# analog_part.net
KiCad netlist of a schematic drawn in Altium Designer
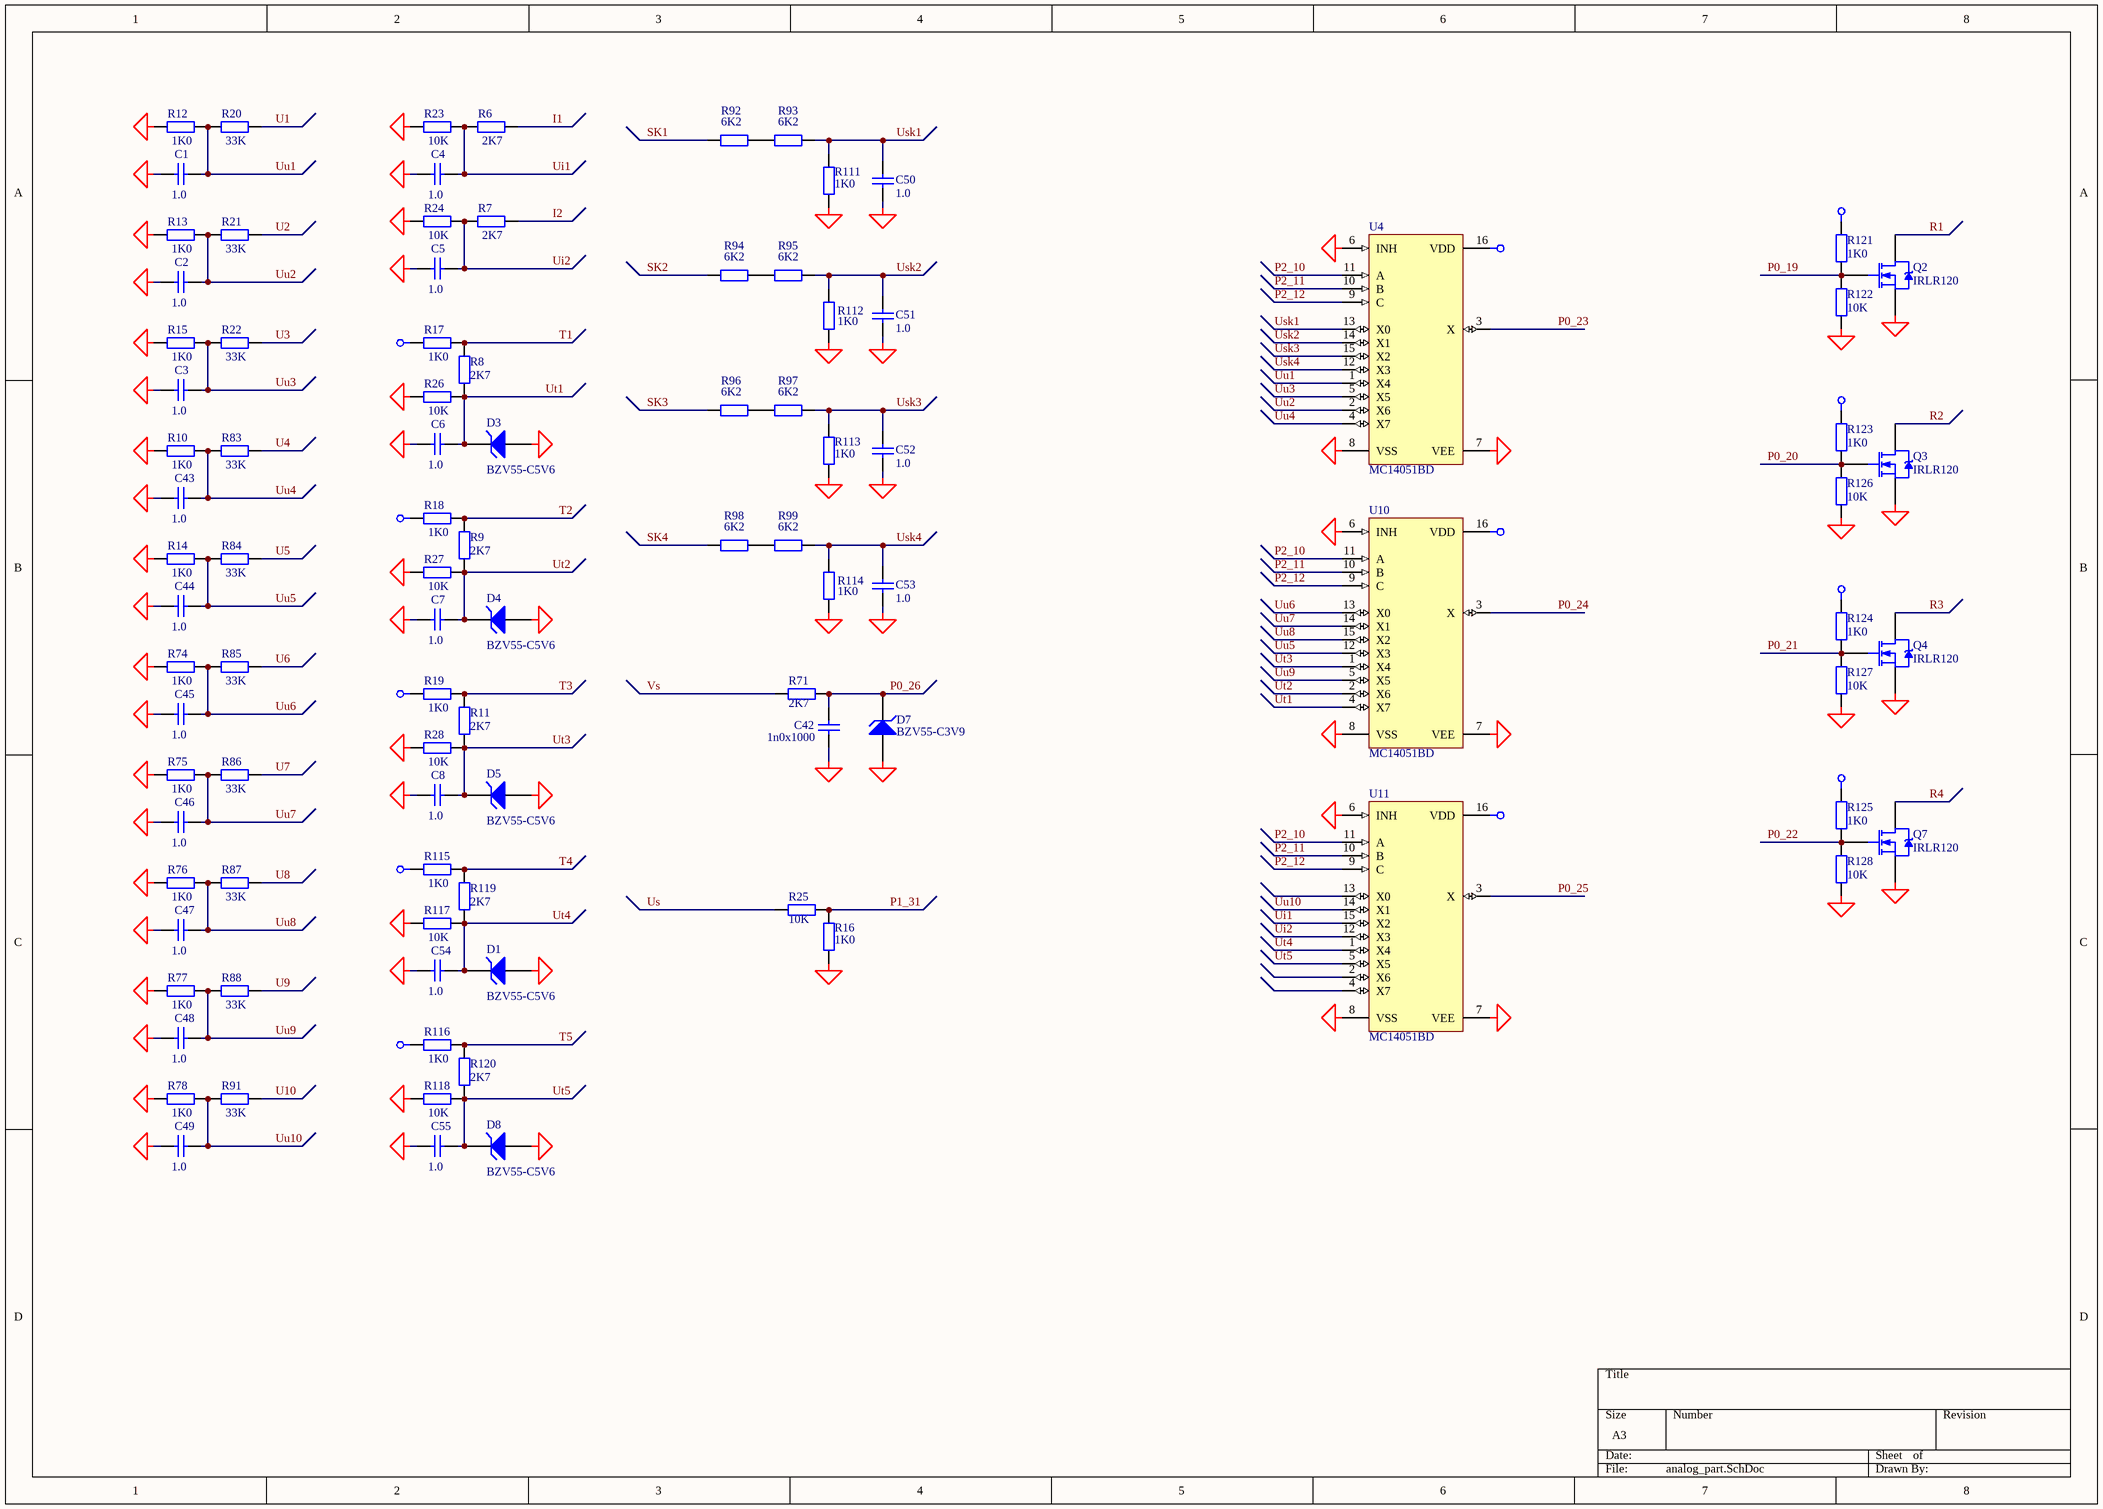
[diagram p0: analog_part.SchDoc]

(export (version "E")
  (design (tool "Eeschema 10.0.6"))
  (components
    (comp (ref "C1")
      (value "1.0")
      (footprint "_1206")
      (description "Capacitor (Semiconductor SIM Model)")
      (fields (field (name "MANUFACTURER") "Generic Components") (field (name "PUBLISHER") "Altium Limited"))
      (libsource (lib "Miscellaneous Devices") (part "Cap Semi"))
    )
    (comp (ref "C2")
      (value "1.0")
      (footprint "_1206")
      (description "Capacitor (Semiconductor SIM Model)")
      (fields (field (name "MANUFACTURER") "Generic Components") (field (name "PUBLISHER") "Altium Limited"))
      (libsource (lib "Miscellaneous Devices") (part "Cap Semi"))
    )
    (comp (ref "C3")
      (value "1.0")
      (footprint "_1206")
      (description "Capacitor (Semiconductor SIM Model)")
      (fields (field (name "MANUFACTURER") "Generic Components") (field (name "PUBLISHER") "Altium Limited"))
      (libsource (lib "Miscellaneous Devices") (part "Cap Semi"))
    )
    (comp (ref "C4")
      (value "1.0")
      (footprint "_1206")
      (description "Capacitor (Semiconductor SIM Model)")
      (fields (field (name "MANUFACTURER") "Generic Components") (field (name "PUBLISHER") "Altium Limited"))
      (libsource (lib "Miscellaneous Devices") (part "Cap Semi"))
    )
    (comp (ref "C5")
      (value "1.0")
      (footprint "_1206")
      (description "Capacitor (Semiconductor SIM Model)")
      (fields (field (name "MANUFACTURER") "Generic Components") (field (name "PUBLISHER") "Altium Limited"))
      (libsource (lib "Miscellaneous Devices") (part "Cap Semi"))
    )
    (comp (ref "C6")
      (value "1.0")
      (footprint "_1206")
      (description "Capacitor (Semiconductor SIM Model)")
      (fields (field (name "MANUFACTURER") "Generic Components") (field (name "PUBLISHER") "Altium Limited"))
      (libsource (lib "Miscellaneous Devices") (part "Cap Semi"))
    )
    (comp (ref "C7")
      (value "1.0")
      (footprint "_1206")
      (description "Capacitor (Semiconductor SIM Model)")
      (fields (field (name "MANUFACTURER") "Generic Components") (field (name "PUBLISHER") "Altium Limited"))
      (libsource (lib "Miscellaneous Devices") (part "Cap Semi"))
    )
    (comp (ref "C8")
      (value "1.0")
      (footprint "_1206")
      (description "Capacitor (Semiconductor SIM Model)")
      (fields (field (name "MANUFACTURER") "Generic Components") (field (name "PUBLISHER") "Altium Limited"))
      (libsource (lib "Miscellaneous Devices") (part "Cap Semi"))
    )
    (comp (ref "C42")
      (value "1n0x1000")
      (footprint "_1206")
      (description "Capacitor (Semiconductor SIM Model)")
      (fields (field (name "MANUFACTURER") "Generic Components") (field (name "PUBLISHER") "Altium Limited"))
      (libsource (lib "") (part "Cap Semi_1"))
    )
    (comp (ref "C43")
      (value "1.0")
      (footprint "_1206")
      (description "Capacitor (Semiconductor SIM Model)")
      (fields (field (name "MANUFACTURER") "Generic Components") (field (name "PUBLISHER") "Altium Limited"))
      (libsource (lib "Miscellaneous Devices") (part "Cap Semi"))
    )
    (comp (ref "C44")
      (value "1.0")
      (footprint "_1206")
      (description "Capacitor (Semiconductor SIM Model)")
      (fields (field (name "MANUFACTURER") "Generic Components") (field (name "PUBLISHER") "Altium Limited"))
      (libsource (lib "Miscellaneous Devices") (part "Cap Semi"))
    )
    (comp (ref "C45")
      (value "1.0")
      (footprint "_1206")
      (description "Capacitor (Semiconductor SIM Model)")
      (fields (field (name "MANUFACTURER") "Generic Components") (field (name "PUBLISHER") "Altium Limited"))
      (libsource (lib "Miscellaneous Devices") (part "Cap Semi"))
    )
    (comp (ref "C46")
      (value "1.0")
      (footprint "_1206")
      (description "Capacitor (Semiconductor SIM Model)")
      (fields (field (name "MANUFACTURER") "Generic Components") (field (name "PUBLISHER") "Altium Limited"))
      (libsource (lib "Miscellaneous Devices") (part "Cap Semi"))
    )
    (comp (ref "C47")
      (value "1.0")
      (footprint "_1206")
      (description "Capacitor (Semiconductor SIM Model)")
      (fields (field (name "MANUFACTURER") "Generic Components") (field (name "PUBLISHER") "Altium Limited"))
      (libsource (lib "Miscellaneous Devices") (part "Cap Semi"))
    )
    (comp (ref "C48")
      (value "1.0")
      (footprint "_1206")
      (description "Capacitor (Semiconductor SIM Model)")
      (fields (field (name "MANUFACTURER") "Generic Components") (field (name "PUBLISHER") "Altium Limited"))
      (libsource (lib "Miscellaneous Devices") (part "Cap Semi"))
    )
    (comp (ref "C49")
      (value "1.0")
      (footprint "_1206")
      (description "Capacitor (Semiconductor SIM Model)")
      (fields (field (name "MANUFACTURER") "Generic Components") (field (name "PUBLISHER") "Altium Limited"))
      (libsource (lib "Miscellaneous Devices") (part "Cap Semi"))
    )
    (comp (ref "C50")
      (value "1.0")
      (footprint "_1206")
      (description "Capacitor (Semiconductor SIM Model)")
      (fields (field (name "MANUFACTURER") "Generic Components") (field (name "PUBLISHER") "Altium Limited"))
      (libsource (lib "Miscellaneous Devices") (part "Cap Semi"))
    )
    (comp (ref "C51")
      (value "1.0")
      (footprint "_1206")
      (description "Capacitor (Semiconductor SIM Model)")
      (fields (field (name "MANUFACTURER") "Generic Components") (field (name "PUBLISHER") "Altium Limited"))
      (libsource (lib "Miscellaneous Devices") (part "Cap Semi"))
    )
    (comp (ref "C52")
      (value "1.0")
      (footprint "_1206")
      (description "Capacitor (Semiconductor SIM Model)")
      (fields (field (name "MANUFACTURER") "Generic Components") (field (name "PUBLISHER") "Altium Limited"))
      (libsource (lib "Miscellaneous Devices") (part "Cap Semi"))
    )
    (comp (ref "C53")
      (value "1.0")
      (footprint "_1206")
      (description "Capacitor (Semiconductor SIM Model)")
      (fields (field (name "MANUFACTURER") "Generic Components") (field (name "PUBLISHER") "Altium Limited"))
      (libsource (lib "Miscellaneous Devices") (part "Cap Semi"))
    )
    (comp (ref "C54")
      (value "1.0")
      (footprint "_1206")
      (description "Capacitor (Semiconductor SIM Model)")
      (fields (field (name "MANUFACTURER") "Generic Components") (field (name "PUBLISHER") "Altium Limited"))
      (libsource (lib "Miscellaneous Devices") (part "Cap Semi"))
    )
    (comp (ref "C55")
      (value "1.0")
      (footprint "_1206")
      (description "Capacitor (Semiconductor SIM Model)")
      (fields (field (name "MANUFACTURER") "Generic Components") (field (name "PUBLISHER") "Altium Limited"))
      (libsource (lib "Miscellaneous Devices") (part "Cap Semi"))
    )
    (comp (ref "D1")
      (value "BZV55-C5V6")
      (footprint "_1206d")
      (description "Zener Diode")
      (fields (field (name "MANUFACTURER") "Generic Components") (field (name "PUBLISHER") "Altium Limited"))
      (libsource (lib "Miscellaneous Devices") (part "D Zener"))
    )
    (comp (ref "D3")
      (value "BZV55-C5V6")
      (footprint "_1206d")
      (description "Zener Diode")
      (fields (field (name "MANUFACTURER") "Generic Components") (field (name "PUBLISHER") "Altium Limited"))
      (libsource (lib "Miscellaneous Devices") (part "D Zener"))
    )
    (comp (ref "D4")
      (value "BZV55-C5V6")
      (footprint "_1206d")
      (description "Zener Diode")
      (fields (field (name "MANUFACTURER") "Generic Components") (field (name "PUBLISHER") "Altium Limited"))
      (libsource (lib "Miscellaneous Devices") (part "D Zener"))
    )
    (comp (ref "D5")
      (value "BZV55-C5V6")
      (footprint "_1206d")
      (description "Zener Diode")
      (fields (field (name "MANUFACTURER") "Generic Components") (field (name "PUBLISHER") "Altium Limited"))
      (libsource (lib "Miscellaneous Devices") (part "D Zener"))
    )
    (comp (ref "D7")
      (value "BZV55-C3V9")
      (footprint "_1206d")
      (description "Zener Diode")
      (fields (field (name "MANUFACTURER") "Generic Components") (field (name "PUBLISHER") "Altium Limited"))
      (libsource (lib "") (part "D Zener_1"))
    )
    (comp (ref "D8")
      (value "BZV55-C5V6")
      (footprint "_1206d")
      (description "Zener Diode")
      (fields (field (name "MANUFACTURER") "Generic Components") (field (name "PUBLISHER") "Altium Limited"))
      (libsource (lib "Miscellaneous Devices") (part "D Zener"))
    )
    (comp (ref "Q2")
      (value "IRLR120")
      (footprint "SIP-G3/E8")
      (description "HEXFET N-Channel Power MOSFET")
      (fields
        (field (name "MANUFACTURER") "International Rectifier")
        (field (name "PUBLISHER") "Altium Limited")
      )
      (libsource (lib "IR Discrete MOSFET") (part "IRFR120"))
    )
    (comp (ref "Q3")
      (value "IRLR120")
      (footprint "SIP-G3/E8")
      (description "HEXFET N-Channel Power MOSFET")
      (fields
        (field (name "MANUFACTURER") "International Rectifier")
        (field (name "PUBLISHER") "Altium Limited")
      )
      (libsource (lib "IR Discrete MOSFET") (part "IRFR120"))
    )
    (comp (ref "Q4")
      (value "IRLR120")
      (footprint "SIP-G3/E8")
      (description "HEXFET N-Channel Power MOSFET")
      (fields
        (field (name "MANUFACTURER") "International Rectifier")
        (field (name "PUBLISHER") "Altium Limited")
      )
      (libsource (lib "IR Discrete MOSFET") (part "IRFR120"))
    )
    (comp (ref "Q7")
      (value "IRLR120")
      (footprint "SIP-G3/E8")
      (description "HEXFET N-Channel Power MOSFET")
      (fields
        (field (name "MANUFACTURER") "International Rectifier")
        (field (name "PUBLISHER") "Altium Limited")
      )
      (libsource (lib "IR Discrete MOSFET") (part "IRFR120"))
    )
    (comp (ref "R6")
      (value "2K7")
      (footprint "_1206")
      (description "Resistor")
      (fields (field (name "MANUFACTURER") "Generic Components") (field (name "PUBLISHER") "Altium Limited"))
      (libsource (lib "Miscellaneous Devices") (part "Res2"))
    )
    (comp (ref "R7")
      (value "2K7")
      (footprint "_1206")
      (description "Resistor")
      (fields (field (name "MANUFACTURER") "Generic Components") (field (name "PUBLISHER") "Altium Limited"))
      (libsource (lib "Miscellaneous Devices") (part "Res2"))
    )
    (comp (ref "R8")
      (value "2K7")
      (footprint "_1206")
      (description "Resistor")
      (fields (field (name "MANUFACTURER") "Generic Components") (field (name "PUBLISHER") "Altium Limited"))
      (libsource (lib "") (part "Res2_3"))
    )
    (comp (ref "R9")
      (value "2K7")
      (footprint "_1206")
      (description "Resistor")
      (fields (field (name "MANUFACTURER") "Generic Components") (field (name "PUBLISHER") "Altium Limited"))
      (libsource (lib "") (part "Res2_3"))
    )
    (comp (ref "R10")
      (value "1K0")
      (footprint "_1206")
      (description "Resistor")
      (fields (field (name "MANUFACTURER") "Generic Components") (field (name "PUBLISHER") "Altium Limited"))
      (libsource (lib "") (part "Res2_1"))
    )
    (comp (ref "R11")
      (value "2K7")
      (footprint "_1206")
      (description "Resistor")
      (fields (field (name "MANUFACTURER") "Generic Components") (field (name "PUBLISHER") "Altium Limited"))
      (libsource (lib "") (part "Res2_3"))
    )
    (comp (ref "R12")
      (value "1K0")
      (footprint "_1206")
      (description "Resistor")
      (fields (field (name "MANUFACTURER") "Generic Components") (field (name "PUBLISHER") "Altium Limited"))
      (libsource (lib "") (part "Res2_1"))
    )
    (comp (ref "R13")
      (value "1K0")
      (footprint "_1206")
      (description "Resistor")
      (fields (field (name "MANUFACTURER") "Generic Components") (field (name "PUBLISHER") "Altium Limited"))
      (libsource (lib "") (part "Res2_1"))
    )
    (comp (ref "R14")
      (value "1K0")
      (footprint "_1206")
      (description "Resistor")
      (fields (field (name "MANUFACTURER") "Generic Components") (field (name "PUBLISHER") "Altium Limited"))
      (libsource (lib "") (part "Res2_1"))
    )
    (comp (ref "R15")
      (value "1K0")
      (footprint "_1206")
      (description "Resistor")
      (fields (field (name "MANUFACTURER") "Generic Components") (field (name "PUBLISHER") "Altium Limited"))
      (libsource (lib "") (part "Res2_1"))
    )
    (comp (ref "R16")
      (value "1K0")
      (footprint "_1206")
      (description "Resistor")
      (fields (field (name "MANUFACTURER") "Generic Components") (field (name "PUBLISHER") "Altium Limited"))
      (libsource (lib "") (part "Res2_2"))
    )
    (comp (ref "R17")
      (value "1K0")
      (footprint "_1206")
      (description "Resistor")
      (fields (field (name "MANUFACTURER") "Generic Components") (field (name "PUBLISHER") "Altium Limited"))
      (libsource (lib "") (part "Res2_1"))
    )
    (comp (ref "R18")
      (value "1K0")
      (footprint "_1206")
      (description "Resistor")
      (fields (field (name "MANUFACTURER") "Generic Components") (field (name "PUBLISHER") "Altium Limited"))
      (libsource (lib "") (part "Res2_1"))
    )
    (comp (ref "R19")
      (value "1K0")
      (footprint "_1206")
      (description "Resistor")
      (fields (field (name "MANUFACTURER") "Generic Components") (field (name "PUBLISHER") "Altium Limited"))
      (libsource (lib "") (part "Res2_1"))
    )
    (comp (ref "R20")
      (value "33K")
      (footprint "_1206")
      (description "Resistor")
      (fields (field (name "MANUFACTURER") "Generic Components") (field (name "PUBLISHER") "Altium Limited"))
      (libsource (lib "Miscellaneous Devices") (part "Res2"))
    )
    (comp (ref "R21")
      (value "33K")
      (footprint "_1206")
      (description "Resistor")
      (fields (field (name "MANUFACTURER") "Generic Components") (field (name "PUBLISHER") "Altium Limited"))
      (libsource (lib "Miscellaneous Devices") (part "Res2"))
    )
    (comp (ref "R22")
      (value "33K")
      (footprint "_1206")
      (description "Resistor")
      (fields (field (name "MANUFACTURER") "Generic Components") (field (name "PUBLISHER") "Altium Limited"))
      (libsource (lib "Miscellaneous Devices") (part "Res2"))
    )
    (comp (ref "R23")
      (value "10K")
      (footprint "_1206")
      (description "Resistor")
      (fields (field (name "MANUFACTURER") "Generic Components") (field (name "PUBLISHER") "Altium Limited"))
      (libsource (lib "Miscellaneous Devices") (part "Res2"))
    )
    (comp (ref "R24")
      (value "10K")
      (footprint "_1206")
      (description "Resistor")
      (fields (field (name "MANUFACTURER") "Generic Components") (field (name "PUBLISHER") "Altium Limited"))
      (libsource (lib "Miscellaneous Devices") (part "Res2"))
    )
    (comp (ref "R25")
      (value "10K")
      (footprint "_1206")
      (description "Resistor")
      (fields (field (name "MANUFACTURER") "Generic Components") (field (name "PUBLISHER") "Altium Limited"))
      (libsource (lib "") (part "Res2_1"))
    )
    (comp (ref "R26")
      (value "10K")
      (footprint "_1206")
      (description "Resistor")
      (fields (field (name "MANUFACTURER") "Generic Components") (field (name "PUBLISHER") "Altium Limited"))
      (libsource (lib "Miscellaneous Devices") (part "Res2"))
    )
    (comp (ref "R27")
      (value "10K")
      (footprint "_1206")
      (description "Resistor")
      (fields (field (name "MANUFACTURER") "Generic Components") (field (name "PUBLISHER") "Altium Limited"))
      (libsource (lib "Miscellaneous Devices") (part "Res2"))
    )
    (comp (ref "R28")
      (value "10K")
      (footprint "_1206")
      (description "Resistor")
      (fields (field (name "MANUFACTURER") "Generic Components") (field (name "PUBLISHER") "Altium Limited"))
      (libsource (lib "Miscellaneous Devices") (part "Res2"))
    )
    (comp (ref "R71")
      (value "2K7")
      (footprint "_1206")
      (description "Resistor")
      (fields (field (name "MANUFACTURER") "Generic Components") (field (name "PUBLISHER") "Altium Limited"))
      (libsource (lib "") (part "Res2_4"))
    )
    (comp (ref "R74")
      (value "1K0")
      (footprint "_1206")
      (description "Resistor")
      (fields (field (name "MANUFACTURER") "Generic Components") (field (name "PUBLISHER") "Altium Limited"))
      (libsource (lib "") (part "Res2_1"))
    )
    (comp (ref "R75")
      (value "1K0")
      (footprint "_1206")
      (description "Resistor")
      (fields (field (name "MANUFACTURER") "Generic Components") (field (name "PUBLISHER") "Altium Limited"))
      (libsource (lib "") (part "Res2_1"))
    )
    (comp (ref "R76")
      (value "1K0")
      (footprint "_1206")
      (description "Resistor")
      (fields (field (name "MANUFACTURER") "Generic Components") (field (name "PUBLISHER") "Altium Limited"))
      (libsource (lib "") (part "Res2_1"))
    )
    (comp (ref "R77")
      (value "1K0")
      (footprint "_1206")
      (description "Resistor")
      (fields (field (name "MANUFACTURER") "Generic Components") (field (name "PUBLISHER") "Altium Limited"))
      (libsource (lib "") (part "Res2_1"))
    )
    (comp (ref "R78")
      (value "1K0")
      (footprint "_1206")
      (description "Resistor")
      (fields (field (name "MANUFACTURER") "Generic Components") (field (name "PUBLISHER") "Altium Limited"))
      (libsource (lib "") (part "Res2_1"))
    )
    (comp (ref "R83")
      (value "33K")
      (footprint "_1206")
      (description "Resistor")
      (fields (field (name "MANUFACTURER") "Generic Components") (field (name "PUBLISHER") "Altium Limited"))
      (libsource (lib "Miscellaneous Devices") (part "Res2"))
    )
    (comp (ref "R84")
      (value "33K")
      (footprint "_1206")
      (description "Resistor")
      (fields (field (name "MANUFACTURER") "Generic Components") (field (name "PUBLISHER") "Altium Limited"))
      (libsource (lib "Miscellaneous Devices") (part "Res2"))
    )
    (comp (ref "R85")
      (value "33K")
      (footprint "_1206")
      (description "Resistor")
      (fields (field (name "MANUFACTURER") "Generic Components") (field (name "PUBLISHER") "Altium Limited"))
      (libsource (lib "Miscellaneous Devices") (part "Res2"))
    )
    (comp (ref "R86")
      (value "33K")
      (footprint "_1206")
      (description "Resistor")
      (fields (field (name "MANUFACTURER") "Generic Components") (field (name "PUBLISHER") "Altium Limited"))
      (libsource (lib "Miscellaneous Devices") (part "Res2"))
    )
    (comp (ref "R87")
      (value "33K")
      (footprint "_1206")
      (description "Resistor")
      (fields (field (name "MANUFACTURER") "Generic Components") (field (name "PUBLISHER") "Altium Limited"))
      (libsource (lib "Miscellaneous Devices") (part "Res2"))
    )
    (comp (ref "R88")
      (value "33K")
      (footprint "_1206")
      (description "Resistor")
      (fields (field (name "MANUFACTURER") "Generic Components") (field (name "PUBLISHER") "Altium Limited"))
      (libsource (lib "Miscellaneous Devices") (part "Res2"))
    )
    (comp (ref "R91")
      (value "33K")
      (footprint "_1206")
      (description "Resistor")
      (fields (field (name "MANUFACTURER") "Generic Components") (field (name "PUBLISHER") "Altium Limited"))
      (libsource (lib "Miscellaneous Devices") (part "Res2"))
    )
    (comp (ref "R92")
      (value "6K2")
      (footprint "_1206")
      (description "Resistor")
      (fields (field (name "MANUFACTURER") "Generic Components") (field (name "PUBLISHER") "Altium Limited"))
      (libsource (lib "Miscellaneous Devices") (part "Res2"))
    )
    (comp (ref "R93")
      (value "6K2")
      (footprint "_1206")
      (description "Resistor")
      (fields (field (name "MANUFACTURER") "Generic Components") (field (name "PUBLISHER") "Altium Limited"))
      (libsource (lib "Miscellaneous Devices") (part "Res2"))
    )
    (comp (ref "R94")
      (value "6K2")
      (footprint "_1206")
      (description "Resistor")
      (fields (field (name "MANUFACTURER") "Generic Components") (field (name "PUBLISHER") "Altium Limited"))
      (libsource (lib "Miscellaneous Devices") (part "Res2"))
    )
    (comp (ref "R95")
      (value "6K2")
      (footprint "_1206")
      (description "Resistor")
      (fields (field (name "MANUFACTURER") "Generic Components") (field (name "PUBLISHER") "Altium Limited"))
      (libsource (lib "Miscellaneous Devices") (part "Res2"))
    )
    (comp (ref "R96")
      (value "6K2")
      (footprint "_1206")
      (description "Resistor")
      (fields (field (name "MANUFACTURER") "Generic Components") (field (name "PUBLISHER") "Altium Limited"))
      (libsource (lib "Miscellaneous Devices") (part "Res2"))
    )
    (comp (ref "R97")
      (value "6K2")
      (footprint "_1206")
      (description "Resistor")
      (fields (field (name "MANUFACTURER") "Generic Components") (field (name "PUBLISHER") "Altium Limited"))
      (libsource (lib "Miscellaneous Devices") (part "Res2"))
    )
    (comp (ref "R98")
      (value "6K2")
      (footprint "_1206")
      (description "Resistor")
      (fields (field (name "MANUFACTURER") "Generic Components") (field (name "PUBLISHER") "Altium Limited"))
      (libsource (lib "Miscellaneous Devices") (part "Res2"))
    )
    (comp (ref "R99")
      (value "6K2")
      (footprint "_1206")
      (description "Resistor")
      (fields (field (name "MANUFACTURER") "Generic Components") (field (name "PUBLISHER") "Altium Limited"))
      (libsource (lib "Miscellaneous Devices") (part "Res2"))
    )
    (comp (ref "R111")
      (value "1K0")
      (footprint "_1206")
      (description "Resistor")
      (fields (field (name "MANUFACTURER") "Generic Components") (field (name "PUBLISHER") "Altium Limited"))
      (libsource (lib "") (part "Res2_3"))
    )
    (comp (ref "R112")
      (value "1K0")
      (footprint "_1206")
      (description "Resistor")
      (fields (field (name "MANUFACTURER") "Generic Components") (field (name "PUBLISHER") "Altium Limited"))
      (libsource (lib "") (part "Res2_3"))
    )
    (comp (ref "R113")
      (value "1K0")
      (footprint "_1206")
      (description "Resistor")
      (fields (field (name "MANUFACTURER") "Generic Components") (field (name "PUBLISHER") "Altium Limited"))
      (libsource (lib "") (part "Res2_3"))
    )
    (comp (ref "R114")
      (value "1K0")
      (footprint "_1206")
      (description "Resistor")
      (fields (field (name "MANUFACTURER") "Generic Components") (field (name "PUBLISHER") "Altium Limited"))
      (libsource (lib "") (part "Res2_3"))
    )
    (comp (ref "R115")
      (value "1K0")
      (footprint "_1206")
      (description "Resistor")
      (fields (field (name "MANUFACTURER") "Generic Components") (field (name "PUBLISHER") "Altium Limited"))
      (libsource (lib "") (part "Res2_1"))
    )
    (comp (ref "R116")
      (value "1K0")
      (footprint "_1206")
      (description "Resistor")
      (fields (field (name "MANUFACTURER") "Generic Components") (field (name "PUBLISHER") "Altium Limited"))
      (libsource (lib "") (part "Res2_1"))
    )
    (comp (ref "R117")
      (value "10K")
      (footprint "_1206")
      (description "Resistor")
      (fields (field (name "MANUFACTURER") "Generic Components") (field (name "PUBLISHER") "Altium Limited"))
      (libsource (lib "Miscellaneous Devices") (part "Res2"))
    )
    (comp (ref "R118")
      (value "10K")
      (footprint "_1206")
      (description "Resistor")
      (fields (field (name "MANUFACTURER") "Generic Components") (field (name "PUBLISHER") "Altium Limited"))
      (libsource (lib "Miscellaneous Devices") (part "Res2"))
    )
    (comp (ref "R119")
      (value "2K7")
      (footprint "_1206")
      (description "Resistor")
      (fields (field (name "MANUFACTURER") "Generic Components") (field (name "PUBLISHER") "Altium Limited"))
      (libsource (lib "") (part "Res2_3"))
    )
    (comp (ref "R120")
      (value "2K7")
      (footprint "_1206")
      (description "Resistor")
      (fields (field (name "MANUFACTURER") "Generic Components") (field (name "PUBLISHER") "Altium Limited"))
      (libsource (lib "") (part "Res2_3"))
    )
    (comp (ref "R121")
      (value "1K0")
      (footprint "_1206")
      (description "Resistor")
      (fields (field (name "MANUFACTURER") "Generic Components") (field (name "PUBLISHER") "Altium Limited"))
      (libsource (lib "") (part "Res2_3"))
    )
    (comp (ref "R122")
      (value "10K")
      (footprint "_1206")
      (description "Resistor")
      (fields (field (name "MANUFACTURER") "Generic Components") (field (name "PUBLISHER") "Altium Limited"))
      (libsource (lib "") (part "Res2_2"))
    )
    (comp (ref "R123")
      (value "1K0")
      (footprint "_1206")
      (description "Resistor")
      (fields (field (name "MANUFACTURER") "Generic Components") (field (name "PUBLISHER") "Altium Limited"))
      (libsource (lib "") (part "Res2_3"))
    )
    (comp (ref "R124")
      (value "1K0")
      (footprint "_1206")
      (description "Resistor")
      (fields (field (name "MANUFACTURER") "Generic Components") (field (name "PUBLISHER") "Altium Limited"))
      (libsource (lib "") (part "Res2_3"))
    )
    (comp (ref "R125")
      (value "1K0")
      (footprint "_1206")
      (description "Resistor")
      (fields (field (name "MANUFACTURER") "Generic Components") (field (name "PUBLISHER") "Altium Limited"))
      (libsource (lib "") (part "Res2_3"))
    )
    (comp (ref "R126")
      (value "10K")
      (footprint "_1206")
      (description "Resistor")
      (fields (field (name "MANUFACTURER") "Generic Components") (field (name "PUBLISHER") "Altium Limited"))
      (libsource (lib "") (part "Res2_2"))
    )
    (comp (ref "R127")
      (value "10K")
      (footprint "_1206")
      (description "Resistor")
      (fields (field (name "MANUFACTURER") "Generic Components") (field (name "PUBLISHER") "Altium Limited"))
      (libsource (lib "") (part "Res2_2"))
    )
    (comp (ref "R128")
      (value "10K")
      (footprint "_1206")
      (description "Resistor")
      (fields (field (name "MANUFACTURER") "Generic Components") (field (name "PUBLISHER") "Altium Limited"))
      (libsource (lib "") (part "Res2_2"))
    )
    (comp (ref "U4")
      (value "MC14051BD")
      (footprint "SO-G16/C5.85")
      (description "8-Channel Analog Multiplexer/Demultiplexer")
      (fields (field (name "MANUFACTURER") "ON Semiconductor") (field (name "PUBLISHER") "Altium Limited"))
      (libsource (lib "ON Semi Logic Multiplexer") (part "MC14051BD"))
    )
    (comp (ref "U10")
      (value "MC14051BD")
      (footprint "SO-G16/C5.85")
      (description "8-Channel Analog Multiplexer/Demultiplexer")
      (fields (field (name "MANUFACTURER") "ON Semiconductor") (field (name "PUBLISHER") "Altium Limited"))
      (libsource (lib "ON Semi Logic Multiplexer") (part "MC14051BD"))
    )
    (comp (ref "U11")
      (value "MC14051BD")
      (footprint "SO-G16/C5.85")
      (description "8-Channel Analog Multiplexer/Demultiplexer")
      (fields (field (name "MANUFACTURER") "ON Semiconductor") (field (name "PUBLISHER") "Altium Limited"))
      (libsource (lib "ON Semi Logic Multiplexer") (part "MC14051BD"))
    )
  )
  (nets
    (net (code "1") (name "+3v3") (class "Default")
      (node (ref "U10") (pin "16") (pinfunction "VDD_16") (pintype "power_in"))
      (node (ref "U11") (pin "16") (pinfunction "VDD_16") (pintype "power_in"))
      (node (ref "U4") (pin "16") (pinfunction "VDD_16") (pintype "power_in"))
    )
    (net (code "2") (name "+5v") (class "Default")
      (node (ref "R115") (pin "2") (pinfunction "2_2") (pintype "passive"))
      (node (ref "R116") (pin "2") (pinfunction "2_2") (pintype "passive"))
      (node (ref "R121") (pin "2") (pinfunction "2_2") (pintype "passive"))
      (node (ref "R123") (pin "2") (pinfunction "2_2") (pintype "passive"))
      (node (ref "R124") (pin "2") (pinfunction "2_2") (pintype "passive"))
      (node (ref "R125") (pin "2") (pinfunction "2_2") (pintype "passive"))
      (node (ref "R17") (pin "2") (pinfunction "2_2") (pintype "passive"))
      (node (ref "R18") (pin "2") (pinfunction "2_2") (pintype "passive"))
      (node (ref "R19") (pin "2") (pinfunction "2_2") (pintype "passive"))
    )
    (net (code "3") (name "/I1") (class "Default")
      (node (ref "R6") (pin "2") (pinfunction "2_2") (pintype "passive"))
    )
    (net (code "4") (name "/I2") (class "Default")
      (node (ref "R7") (pin "2") (pinfunction "2_2") (pintype "passive"))
    )
    (net (code "5") (name "/P0_19") (class "Default")
      (node (ref "Q2") (pin "1") (pinfunction "G_1") (pintype "passive"))
      (node (ref "R121") (pin "1") (pinfunction "1_1") (pintype "passive"))
      (node (ref "R122") (pin "1") (pinfunction "1_1") (pintype "passive"))
    )
    (net (code "6") (name "/P0_20") (class "Default")
      (node (ref "Q3") (pin "1") (pinfunction "G_1") (pintype "passive"))
      (node (ref "R123") (pin "1") (pinfunction "1_1") (pintype "passive"))
      (node (ref "R126") (pin "1") (pinfunction "1_1") (pintype "passive"))
    )
    (net (code "7") (name "/P0_21") (class "Default")
      (node (ref "Q4") (pin "1") (pinfunction "G_1") (pintype "passive"))
      (node (ref "R124") (pin "1") (pinfunction "1_1") (pintype "passive"))
      (node (ref "R127") (pin "1") (pinfunction "1_1") (pintype "passive"))
    )
    (net (code "8") (name "/P0_22") (class "Default")
      (node (ref "Q7") (pin "1") (pinfunction "G_1") (pintype "passive"))
      (node (ref "R125") (pin "1") (pinfunction "1_1") (pintype "passive"))
      (node (ref "R128") (pin "1") (pinfunction "1_1") (pintype "passive"))
    )
    (net (code "9") (name "/P0_23") (class "Default")
      (node (ref "U4") (pin "3") (pinfunction "X_3") (pintype "bidirectional"))
    )
    (net (code "10") (name "/P0_24") (class "Default")
      (node (ref "U10") (pin "3") (pinfunction "X_3") (pintype "bidirectional"))
    )
    (net (code "11") (name "/P0_25") (class "Default")
      (node (ref "U11") (pin "3") (pinfunction "X_3") (pintype "bidirectional"))
    )
    (net (code "12") (name "/P0_26") (class "Default")
      (node (ref "C42") (pin "1") (pinfunction "1_1") (pintype "passive"))
      (node (ref "D7") (pin "2") (pinfunction "K_2") (pintype "passive"))
      (node (ref "R71") (pin "1") (pinfunction "1_1") (pintype "passive"))
    )
    (net (code "13") (name "/P1_31") (class "Default")
      (node (ref "R16") (pin "1") (pinfunction "1_1") (pintype "passive"))
      (node (ref "R25") (pin "1") (pinfunction "1_1") (pintype "passive"))
    )
    (net (code "14") (name "/P2_10") (class "Default")
      (node (ref "U10") (pin "11") (pinfunction "A_11") (pintype "input"))
      (node (ref "U11") (pin "11") (pinfunction "A_11") (pintype "input"))
      (node (ref "U4") (pin "11") (pinfunction "A_11") (pintype "input"))
    )
    (net (code "15") (name "/P2_11") (class "Default")
      (node (ref "U10") (pin "10") (pinfunction "B_10") (pintype "input"))
      (node (ref "U11") (pin "10") (pinfunction "B_10") (pintype "input"))
      (node (ref "U4") (pin "10") (pinfunction "B_10") (pintype "input"))
    )
    (net (code "16") (name "/P2_12") (class "Default")
      (node (ref "U10") (pin "9") (pinfunction "C_9") (pintype "input"))
      (node (ref "U11") (pin "9") (pinfunction "C_9") (pintype "input"))
      (node (ref "U4") (pin "9") (pinfunction "C_9") (pintype "input"))
    )
    (net (code "17") (name "/R1") (class "Default")
      (node (ref "Q2") (pin "4") (pinfunction "D_4") (pintype "passive"))
    )
    (net (code "18") (name "/R2") (class "Default")
      (node (ref "Q3") (pin "4") (pinfunction "D_4") (pintype "passive"))
    )
    (net (code "19") (name "/R3") (class "Default")
      (node (ref "Q4") (pin "4") (pinfunction "D_4") (pintype "passive"))
    )
    (net (code "20") (name "/R4") (class "Default")
      (node (ref "Q7") (pin "4") (pinfunction "D_4") (pintype "passive"))
    )
    (net (code "21") (name "/SK1") (class "Default")
      (node (ref "R92") (pin "1") (pinfunction "1_1") (pintype "passive"))
    )
    (net (code "22") (name "/SK2") (class "Default")
      (node (ref "R94") (pin "1") (pinfunction "1_1") (pintype "passive"))
    )
    (net (code "23") (name "/SK3") (class "Default")
      (node (ref "R96") (pin "1") (pinfunction "1_1") (pintype "passive"))
    )
    (net (code "24") (name "/SK4") (class "Default")
      (node (ref "R98") (pin "1") (pinfunction "1_1") (pintype "passive"))
    )
    (net (code "25") (name "/T1") (class "Default")
      (node (ref "R17") (pin "1") (pinfunction "1_1") (pintype "passive"))
      (node (ref "R8") (pin "2") (pinfunction "2_2") (pintype "passive"))
    )
    (net (code "26") (name "/T2") (class "Default")
      (node (ref "R18") (pin "1") (pinfunction "1_1") (pintype "passive"))
      (node (ref "R9") (pin "2") (pinfunction "2_2") (pintype "passive"))
    )
    (net (code "27") (name "/T3") (class "Default")
      (node (ref "R11") (pin "2") (pinfunction "2_2") (pintype "passive"))
      (node (ref "R19") (pin "1") (pinfunction "1_1") (pintype "passive"))
    )
    (net (code "28") (name "/T4") (class "Default")
      (node (ref "R115") (pin "1") (pinfunction "1_1") (pintype "passive"))
      (node (ref "R119") (pin "2") (pinfunction "2_2") (pintype "passive"))
    )
    (net (code "29") (name "/T5") (class "Default")
      (node (ref "R116") (pin "1") (pinfunction "1_1") (pintype "passive"))
      (node (ref "R120") (pin "2") (pinfunction "2_2") (pintype "passive"))
    )
    (net (code "30") (name "/U1") (class "Default")
      (node (ref "R20") (pin "2") (pinfunction "2_2") (pintype "passive"))
    )
    (net (code "31") (name "/U2") (class "Default")
      (node (ref "R21") (pin "2") (pinfunction "2_2") (pintype "passive"))
    )
    (net (code "32") (name "/U3") (class "Default")
      (node (ref "R22") (pin "2") (pinfunction "2_2") (pintype "passive"))
    )
    (net (code "33") (name "/U4") (class "Default")
      (node (ref "R83") (pin "2") (pinfunction "2_2") (pintype "passive"))
    )
    (net (code "34") (name "/U5") (class "Default")
      (node (ref "R84") (pin "2") (pinfunction "2_2") (pintype "passive"))
    )
    (net (code "35") (name "/U6") (class "Default")
      (node (ref "R85") (pin "2") (pinfunction "2_2") (pintype "passive"))
    )
    (net (code "36") (name "/U7") (class "Default")
      (node (ref "R86") (pin "2") (pinfunction "2_2") (pintype "passive"))
    )
    (net (code "37") (name "/U8") (class "Default")
      (node (ref "R87") (pin "2") (pinfunction "2_2") (pintype "passive"))
    )
    (net (code "38") (name "/U9") (class "Default")
      (node (ref "R88") (pin "2") (pinfunction "2_2") (pintype "passive"))
    )
    (net (code "39") (name "/U10") (class "Default")
      (node (ref "R91") (pin "2") (pinfunction "2_2") (pintype "passive"))
    )
    (net (code "40") (name "/Ui1") (class "Default")
      (node (ref "C4") (pin "1") (pinfunction "1_1") (pintype "passive"))
      (node (ref "R23") (pin "2") (pinfunction "2_2") (pintype "passive"))
      (node (ref "R6") (pin "1") (pinfunction "1_1") (pintype "passive"))
      (node (ref "U11") (pin "15") (pinfunction "X2_15") (pintype "bidirectional"))
    )
    (net (code "41") (name "/Ui2") (class "Default")
      (node (ref "C5") (pin "1") (pinfunction "1_1") (pintype "passive"))
      (node (ref "R24") (pin "2") (pinfunction "2_2") (pintype "passive"))
      (node (ref "R7") (pin "1") (pinfunction "1_1") (pintype "passive"))
      (node (ref "U11") (pin "12") (pinfunction "X3_12") (pintype "bidirectional"))
    )
    (net (code "42") (name "/Us") (class "Default")
      (node (ref "R25") (pin "2") (pinfunction "2_2") (pintype "passive"))
    )
    (net (code "43") (name "/Usk1") (class "Default")
      (node (ref "C50") (pin "1") (pinfunction "1_1") (pintype "passive"))
      (node (ref "R111") (pin "2") (pinfunction "2_2") (pintype "passive"))
      (node (ref "R93") (pin "2") (pinfunction "2_2") (pintype "passive"))
      (node (ref "U4") (pin "13") (pinfunction "X0_13") (pintype "bidirectional"))
    )
    (net (code "44") (name "/Usk2") (class "Default")
      (node (ref "C51") (pin "1") (pinfunction "1_1") (pintype "passive"))
      (node (ref "R112") (pin "2") (pinfunction "2_2") (pintype "passive"))
      (node (ref "R95") (pin "2") (pinfunction "2_2") (pintype "passive"))
      (node (ref "U4") (pin "14") (pinfunction "X1_14") (pintype "bidirectional"))
    )
    (net (code "45") (name "/Usk3") (class "Default")
      (node (ref "C52") (pin "1") (pinfunction "1_1") (pintype "passive"))
      (node (ref "R113") (pin "2") (pinfunction "2_2") (pintype "passive"))
      (node (ref "R97") (pin "2") (pinfunction "2_2") (pintype "passive"))
      (node (ref "U4") (pin "15") (pinfunction "X2_15") (pintype "bidirectional"))
    )
    (net (code "46") (name "/Usk4") (class "Default")
      (node (ref "C53") (pin "1") (pinfunction "1_1") (pintype "passive"))
      (node (ref "R114") (pin "2") (pinfunction "2_2") (pintype "passive"))
      (node (ref "R99") (pin "2") (pinfunction "2_2") (pintype "passive"))
      (node (ref "U4") (pin "12") (pinfunction "X3_12") (pintype "bidirectional"))
    )
    (net (code "47") (name "/Ut1") (class "Default")
      (node (ref "C6") (pin "1") (pinfunction "1_1") (pintype "passive"))
      (node (ref "D3") (pin "2") (pinfunction "K_2") (pintype "passive"))
      (node (ref "R26") (pin "2") (pinfunction "2_2") (pintype "passive"))
      (node (ref "R8") (pin "1") (pinfunction "1_1") (pintype "passive"))
      (node (ref "U10") (pin "4") (pinfunction "X7_4") (pintype "bidirectional"))
    )
    (net (code "48") (name "/Ut2") (class "Default")
      (node (ref "C7") (pin "1") (pinfunction "1_1") (pintype "passive"))
      (node (ref "D4") (pin "2") (pinfunction "K_2") (pintype "passive"))
      (node (ref "R27") (pin "2") (pinfunction "2_2") (pintype "passive"))
      (node (ref "R9") (pin "1") (pinfunction "1_1") (pintype "passive"))
      (node (ref "U10") (pin "2") (pinfunction "X6_2") (pintype "bidirectional"))
    )
    (net (code "49") (name "/Ut3") (class "Default")
      (node (ref "C8") (pin "1") (pinfunction "1_1") (pintype "passive"))
      (node (ref "D5") (pin "2") (pinfunction "K_2") (pintype "passive"))
      (node (ref "R11") (pin "1") (pinfunction "1_1") (pintype "passive"))
      (node (ref "R28") (pin "2") (pinfunction "2_2") (pintype "passive"))
      (node (ref "U10") (pin "1") (pinfunction "X4_1") (pintype "bidirectional"))
    )
    (net (code "50") (name "/Ut4") (class "Default")
      (node (ref "C54") (pin "1") (pinfunction "1_1") (pintype "passive"))
      (node (ref "D1") (pin "2") (pinfunction "K_2") (pintype "passive"))
      (node (ref "R117") (pin "2") (pinfunction "2_2") (pintype "passive"))
      (node (ref "R119") (pin "1") (pinfunction "1_1") (pintype "passive"))
      (node (ref "U11") (pin "1") (pinfunction "X4_1") (pintype "bidirectional"))
    )
    (net (code "51") (name "/Ut5") (class "Default")
      (node (ref "C55") (pin "1") (pinfunction "1_1") (pintype "passive"))
      (node (ref "D8") (pin "2") (pinfunction "K_2") (pintype "passive"))
      (node (ref "R118") (pin "2") (pinfunction "2_2") (pintype "passive"))
      (node (ref "R120") (pin "1") (pinfunction "1_1") (pintype "passive"))
      (node (ref "U11") (pin "5") (pinfunction "X5_5") (pintype "bidirectional"))
    )
    (net (code "52") (name "/Uu1") (class "Default")
      (node (ref "C1") (pin "1") (pinfunction "1_1") (pintype "passive"))
      (node (ref "R12") (pin "1") (pinfunction "1_1") (pintype "passive"))
      (node (ref "R20") (pin "1") (pinfunction "1_1") (pintype "passive"))
      (node (ref "U4") (pin "1") (pinfunction "X4_1") (pintype "bidirectional"))
    )
    (net (code "53") (name "/Uu2") (class "Default")
      (node (ref "C2") (pin "1") (pinfunction "1_1") (pintype "passive"))
      (node (ref "R13") (pin "1") (pinfunction "1_1") (pintype "passive"))
      (node (ref "R21") (pin "1") (pinfunction "1_1") (pintype "passive"))
      (node (ref "U4") (pin "2") (pinfunction "X6_2") (pintype "bidirectional"))
    )
    (net (code "54") (name "/Uu3") (class "Default")
      (node (ref "C3") (pin "1") (pinfunction "1_1") (pintype "passive"))
      (node (ref "R15") (pin "1") (pinfunction "1_1") (pintype "passive"))
      (node (ref "R22") (pin "1") (pinfunction "1_1") (pintype "passive"))
      (node (ref "U4") (pin "5") (pinfunction "X5_5") (pintype "bidirectional"))
    )
    (net (code "55") (name "/Uu4") (class "Default")
      (node (ref "C43") (pin "1") (pinfunction "1_1") (pintype "passive"))
      (node (ref "R10") (pin "1") (pinfunction "1_1") (pintype "passive"))
      (node (ref "R83") (pin "1") (pinfunction "1_1") (pintype "passive"))
      (node (ref "U4") (pin "4") (pinfunction "X7_4") (pintype "bidirectional"))
    )
    (net (code "56") (name "/Uu5") (class "Default")
      (node (ref "C44") (pin "1") (pinfunction "1_1") (pintype "passive"))
      (node (ref "R14") (pin "1") (pinfunction "1_1") (pintype "passive"))
      (node (ref "R84") (pin "1") (pinfunction "1_1") (pintype "passive"))
      (node (ref "U10") (pin "12") (pinfunction "X3_12") (pintype "bidirectional"))
    )
    (net (code "57") (name "/Uu6") (class "Default")
      (node (ref "C45") (pin "1") (pinfunction "1_1") (pintype "passive"))
      (node (ref "R74") (pin "1") (pinfunction "1_1") (pintype "passive"))
      (node (ref "R85") (pin "1") (pinfunction "1_1") (pintype "passive"))
      (node (ref "U10") (pin "13") (pinfunction "X0_13") (pintype "bidirectional"))
    )
    (net (code "58") (name "/Uu7") (class "Default")
      (node (ref "C46") (pin "1") (pinfunction "1_1") (pintype "passive"))
      (node (ref "R75") (pin "1") (pinfunction "1_1") (pintype "passive"))
      (node (ref "R86") (pin "1") (pinfunction "1_1") (pintype "passive"))
      (node (ref "U10") (pin "14") (pinfunction "X1_14") (pintype "bidirectional"))
    )
    (net (code "59") (name "/Uu8") (class "Default")
      (node (ref "C47") (pin "1") (pinfunction "1_1") (pintype "passive"))
      (node (ref "R76") (pin "1") (pinfunction "1_1") (pintype "passive"))
      (node (ref "R87") (pin "1") (pinfunction "1_1") (pintype "passive"))
      (node (ref "U10") (pin "15") (pinfunction "X2_15") (pintype "bidirectional"))
    )
    (net (code "60") (name "/Uu9") (class "Default")
      (node (ref "C48") (pin "1") (pinfunction "1_1") (pintype "passive"))
      (node (ref "R77") (pin "1") (pinfunction "1_1") (pintype "passive"))
      (node (ref "R88") (pin "1") (pinfunction "1_1") (pintype "passive"))
      (node (ref "U10") (pin "5") (pinfunction "X5_5") (pintype "bidirectional"))
    )
    (net (code "61") (name "/Uu10") (class "Default")
      (node (ref "C49") (pin "1") (pinfunction "1_1") (pintype "passive"))
      (node (ref "R78") (pin "1") (pinfunction "1_1") (pintype "passive"))
      (node (ref "R91") (pin "1") (pinfunction "1_1") (pintype "passive"))
      (node (ref "U11") (pin "14") (pinfunction "X1_14") (pintype "bidirectional"))
    )
    (net (code "62") (name "/Vs") (class "Default")
      (node (ref "R71") (pin "2") (pinfunction "2_2") (pintype "passive"))
    )
    (net (code "63") (name "GND") (class "Default")
      (node (ref "C1") (pin "2") (pinfunction "2_2") (pintype "passive"))
      (node (ref "C2") (pin "2") (pinfunction "2_2") (pintype "passive"))
      (node (ref "C3") (pin "2") (pinfunction "2_2") (pintype "passive"))
      (node (ref "C4") (pin "2") (pinfunction "2_2") (pintype "passive"))
      (node (ref "C42") (pin "2") (pinfunction "2_2") (pintype "passive"))
      (node (ref "C43") (pin "2") (pinfunction "2_2") (pintype "passive"))
      (node (ref "C44") (pin "2") (pinfunction "2_2") (pintype "passive"))
      (node (ref "C45") (pin "2") (pinfunction "2_2") (pintype "passive"))
      (node (ref "C46") (pin "2") (pinfunction "2_2") (pintype "passive"))
      (node (ref "C47") (pin "2") (pinfunction "2_2") (pintype "passive"))
      (node (ref "C48") (pin "2") (pinfunction "2_2") (pintype "passive"))
      (node (ref "C49") (pin "2") (pinfunction "2_2") (pintype "passive"))
      (node (ref "C5") (pin "2") (pinfunction "2_2") (pintype "passive"))
      (node (ref "C50") (pin "2") (pinfunction "2_2") (pintype "passive"))
      (node (ref "C51") (pin "2") (pinfunction "2_2") (pintype "passive"))
      (node (ref "C52") (pin "2") (pinfunction "2_2") (pintype "passive"))
      (node (ref "C53") (pin "2") (pinfunction "2_2") (pintype "passive"))
      (node (ref "C54") (pin "2") (pinfunction "2_2") (pintype "passive"))
      (node (ref "C55") (pin "2") (pinfunction "2_2") (pintype "passive"))
      (node (ref "C6") (pin "2") (pinfunction "2_2") (pintype "passive"))
      (node (ref "C7") (pin "2") (pinfunction "2_2") (pintype "passive"))
      (node (ref "C8") (pin "2") (pinfunction "2_2") (pintype "passive"))
      (node (ref "D1") (pin "1") (pinfunction "A_1") (pintype "passive"))
      (node (ref "D3") (pin "1") (pinfunction "A_1") (pintype "passive"))
      (node (ref "D4") (pin "1") (pinfunction "A_1") (pintype "passive"))
      (node (ref "D5") (pin "1") (pinfunction "A_1") (pintype "passive"))
      (node (ref "D7") (pin "1") (pinfunction "A_1") (pintype "passive"))
      (node (ref "D8") (pin "1") (pinfunction "A_1") (pintype "passive"))
      (node (ref "Q2") (pin "3") (pinfunction "S_3") (pintype "passive"))
      (node (ref "Q3") (pin "3") (pinfunction "S_3") (pintype "passive"))
      (node (ref "Q4") (pin "3") (pinfunction "S_3") (pintype "passive"))
      (node (ref "Q7") (pin "3") (pinfunction "S_3") (pintype "passive"))
      (node (ref "R10") (pin "2") (pinfunction "2_2") (pintype "passive"))
      (node (ref "R111") (pin "1") (pinfunction "1_1") (pintype "passive"))
      (node (ref "R112") (pin "1") (pinfunction "1_1") (pintype "passive"))
      (node (ref "R113") (pin "1") (pinfunction "1_1") (pintype "passive"))
      (node (ref "R114") (pin "1") (pinfunction "1_1") (pintype "passive"))
      (node (ref "R117") (pin "1") (pinfunction "1_1") (pintype "passive"))
      (node (ref "R118") (pin "1") (pinfunction "1_1") (pintype "passive"))
      (node (ref "R12") (pin "2") (pinfunction "2_2") (pintype "passive"))
      (node (ref "R122") (pin "2") (pinfunction "2_2") (pintype "passive"))
      (node (ref "R126") (pin "2") (pinfunction "2_2") (pintype "passive"))
      (node (ref "R127") (pin "2") (pinfunction "2_2") (pintype "passive"))
      (node (ref "R128") (pin "2") (pinfunction "2_2") (pintype "passive"))
      (node (ref "R13") (pin "2") (pinfunction "2_2") (pintype "passive"))
      (node (ref "R14") (pin "2") (pinfunction "2_2") (pintype "passive"))
      (node (ref "R15") (pin "2") (pinfunction "2_2") (pintype "passive"))
      (node (ref "R16") (pin "2") (pinfunction "2_2") (pintype "passive"))
      (node (ref "R23") (pin "1") (pinfunction "1_1") (pintype "passive"))
      (node (ref "R24") (pin "1") (pinfunction "1_1") (pintype "passive"))
      (node (ref "R26") (pin "1") (pinfunction "1_1") (pintype "passive"))
      (node (ref "R27") (pin "1") (pinfunction "1_1") (pintype "passive"))
      (node (ref "R28") (pin "1") (pinfunction "1_1") (pintype "passive"))
      (node (ref "R74") (pin "2") (pinfunction "2_2") (pintype "passive"))
      (node (ref "R75") (pin "2") (pinfunction "2_2") (pintype "passive"))
      (node (ref "R76") (pin "2") (pinfunction "2_2") (pintype "passive"))
      (node (ref "R77") (pin "2") (pinfunction "2_2") (pintype "passive"))
      (node (ref "R78") (pin "2") (pinfunction "2_2") (pintype "passive"))
      (node (ref "U10") (pin "6") (pinfunction "INH_6") (pintype "input"))
      (node (ref "U10") (pin "7") (pinfunction "VEE_7") (pintype "power_in"))
      (node (ref "U10") (pin "8") (pinfunction "VSS_8") (pintype "power_in"))
      (node (ref "U11") (pin "6") (pinfunction "INH_6") (pintype "input"))
      (node (ref "U11") (pin "7") (pinfunction "VEE_7") (pintype "power_in"))
      (node (ref "U11") (pin "8") (pinfunction "VSS_8") (pintype "power_in"))
      (node (ref "U4") (pin "6") (pinfunction "INH_6") (pintype "input"))
      (node (ref "U4") (pin "7") (pinfunction "VEE_7") (pintype "power_in"))
      (node (ref "U4") (pin "8") (pinfunction "VSS_8") (pintype "power_in"))
    )
    (net (code "64") (name "Net-(R92-Pad2)") (class "Default")
      (node (ref "R92") (pin "2") (pinfunction "2_2") (pintype "passive"))
      (node (ref "R93") (pin "1") (pinfunction "1_1") (pintype "passive"))
    )
    (net (code "65") (name "Net-(R94-Pad2)") (class "Default")
      (node (ref "R94") (pin "2") (pinfunction "2_2") (pintype "passive"))
      (node (ref "R95") (pin "1") (pinfunction "1_1") (pintype "passive"))
    )
    (net (code "66") (name "Net-(R96-Pad2)") (class "Default")
      (node (ref "R96") (pin "2") (pinfunction "2_2") (pintype "passive"))
      (node (ref "R97") (pin "1") (pinfunction "1_1") (pintype "passive"))
    )
    (net (code "67") (name "Net-(R98-Pad2)") (class "Default")
      (node (ref "R98") (pin "2") (pinfunction "2_2") (pintype "passive"))
      (node (ref "R99") (pin "1") (pinfunction "1_1") (pintype "passive"))
    )
    (net (code "68") (name "unconnected-(U11-X0-Pad13)") (class "Default")
      (node (ref "U11") (pin "13") (pinfunction "X0_13") (pintype "bidirectional"))
    )
    (net (code "69") (name "unconnected-(U11-X6-Pad2)") (class "Default")
      (node (ref "U11") (pin "2") (pinfunction "X6_2") (pintype "bidirectional"))
    )
    (net (code "70") (name "unconnected-(U11-X7-Pad4)") (class "Default")
      (node (ref "U11") (pin "4") (pinfunction "X7_4") (pintype "bidirectional"))
    )
  )
)
